# tick-display-mk-5_1.net
KiCad netlist of a schematic drawn in EAGLE
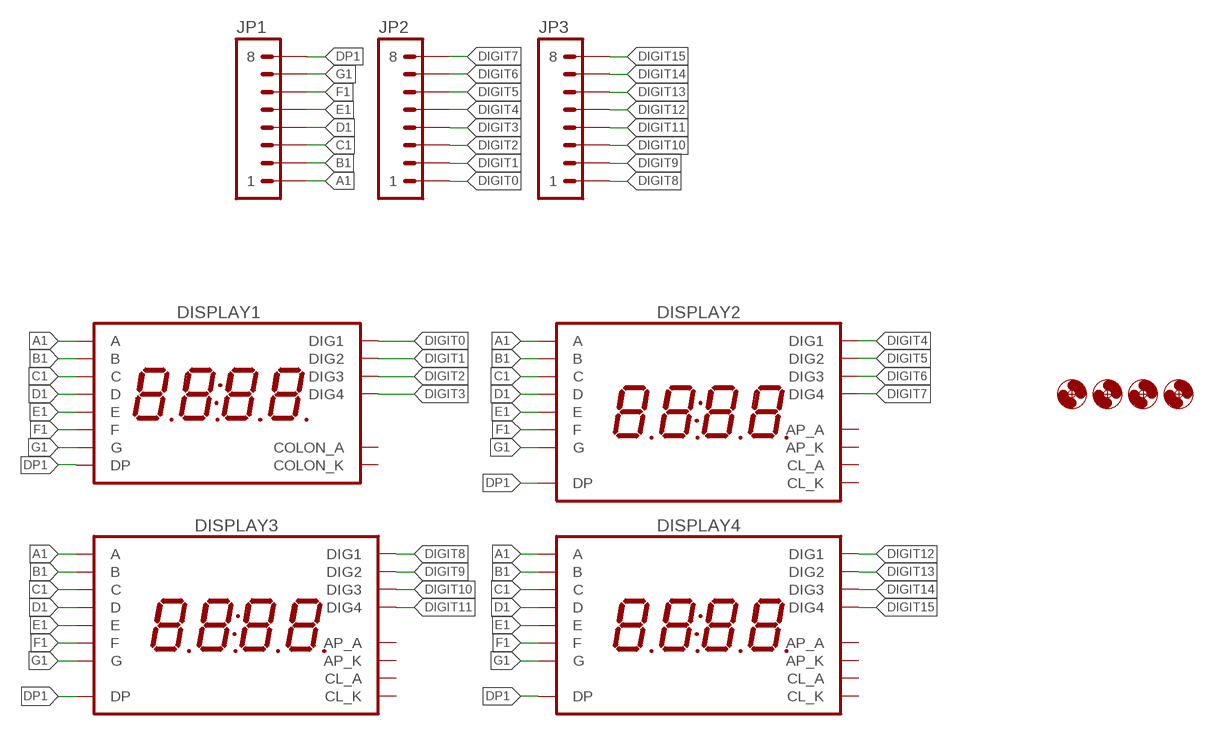
[diagram p0: schematic, sheet 1]

(export (version "E")
  (design (tool "Eeschema 10.0.6"))
  (components
    (comp (ref "DISPLAY1")
      (value "7SEG_4DIGIT_COLON14.2MM-CC")
      (footprint "eagle-import:7SEG_4DIG_0.56IN_14MM_ADAFRUIT")
      (libsource (lib "eagle-import") (part "7SEG_4DIGIT_COLON14.2MM-CC"))
    )
    (comp (ref "DISPLAY2")
      (value "7SEG_4DIGIT_COLON_APOS")
      (footprint "eagle-import:7SEG_4DIG_10MM")
      (libsource (lib "eagle-import") (part "7SEG_4DIGIT_COLON_APOS"))
    )
    (comp (ref "DISPLAY3")
      (value "7SEG_4DIGIT_COLON_APOS")
      (footprint "eagle-import:7SEG_4DIG_10MM")
      (libsource (lib "eagle-import") (part "7SEG_4DIGIT_COLON_APOS"))
    )
    (comp (ref "DISPLAY4")
      (value "7SEG_4DIGIT_COLON_APOS")
      (footprint "eagle-import:7SEG_4DIG_10MM")
      (libsource (lib "eagle-import") (part "7SEG_4DIGIT_COLON_APOS"))
    )
    (comp (ref "H1")
      (value "HOLE#2")
      (footprint "eagle-import:HOLE-#2")
      (libsource (lib "eagle-import") (part "HOLE#2"))
    )
    (comp (ref "H2")
      (value "HOLE#2")
      (footprint "eagle-import:HOLE-#2")
      (libsource (lib "eagle-import") (part "HOLE#2"))
    )
    (comp (ref "H3")
      (value "HOLE#2")
      (footprint "eagle-import:HOLE-#2")
      (libsource (lib "eagle-import") (part "HOLE#2"))
    )
    (comp (ref "H4")
      (value "HOLE#2")
      (footprint "eagle-import:HOLE-#2")
      (libsource (lib "eagle-import") (part "HOLE#2"))
    )
    (comp (ref "JP1")
      (value "M081X08")
      (footprint "eagle-import:1X08")
      (libsource (lib "eagle-import") (part "M081X08"))
    )
    (comp (ref "JP2")
      (value "M081X08")
      (footprint "eagle-import:1X08")
      (libsource (lib "eagle-import") (part "M081X08"))
    )
    (comp (ref "JP3")
      (value "M081X08")
      (footprint "eagle-import:1X08")
      (libsource (lib "eagle-import") (part "M081X08"))
    )
  )
  (nets
    (net (code "1") (name "A1") (class "Default")
      (node (ref "DISPLAY1") (pin "P$13") (pinfunction "A_P$13") (pintype "passive"))
      (node (ref "DISPLAY2") (pin "14") (pinfunction "A_14") (pintype "passive"))
      (node (ref "DISPLAY3") (pin "14") (pinfunction "A_14") (pintype "passive"))
      (node (ref "DISPLAY4") (pin "14") (pinfunction "A_14") (pintype "passive"))
      (node (ref "JP1") (pin "1") (pinfunction "1_1") (pintype "passive"))
    )
    (net (code "2") (name "B1") (class "Default")
      (node (ref "DISPLAY1") (pin "P$9") (pinfunction "B_P$9") (pintype "passive"))
      (node (ref "DISPLAY2") (pin "16") (pinfunction "B_16") (pintype "passive"))
      (node (ref "DISPLAY3") (pin "16") (pinfunction "B_16") (pintype "passive"))
      (node (ref "DISPLAY4") (pin "16") (pinfunction "B_16") (pintype "passive"))
      (node (ref "JP1") (pin "2") (pinfunction "2_2") (pintype "passive"))
    )
    (net (code "3") (name "C1") (class "Default")
      (node (ref "DISPLAY1") (pin "P$4") (pinfunction "C_P$4") (pintype "passive"))
      (node (ref "DISPLAY2") (pin "13") (pinfunction "C_13") (pintype "passive"))
      (node (ref "DISPLAY3") (pin "13") (pinfunction "C_13") (pintype "passive"))
      (node (ref "DISPLAY4") (pin "13") (pinfunction "C_13") (pintype "passive"))
      (node (ref "JP1") (pin "3") (pinfunction "3_3") (pintype "passive"))
    )
    (net (code "4") (name "D1") (class "Default")
      (node (ref "DISPLAY1") (pin "P$2") (pinfunction "D_P$2") (pintype "passive"))
      (node (ref "DISPLAY2") (pin "3") (pinfunction "D_3") (pintype "passive"))
      (node (ref "DISPLAY3") (pin "3") (pinfunction "D_3") (pintype "passive"))
      (node (ref "DISPLAY4") (pin "3") (pinfunction "D_3") (pintype "passive"))
      (node (ref "JP1") (pin "4") (pinfunction "4_4") (pintype "passive"))
    )
    (net (code "5") (name "DIGIT0") (class "Default")
      (node (ref "DISPLAY1") (pin "P$14") (pinfunction "DIG1_P$14") (pintype "passive"))
      (node (ref "JP2") (pin "1") (pinfunction "1_1") (pintype "passive"))
    )
    (net (code "6") (name "DIGIT1") (class "Default")
      (node (ref "DISPLAY1") (pin "P$11") (pinfunction "DIG2_P$11") (pintype "passive"))
      (node (ref "JP2") (pin "2") (pinfunction "2_2") (pintype "passive"))
    )
    (net (code "7") (name "DIGIT2") (class "Default")
      (node (ref "DISPLAY1") (pin "P$10") (pinfunction "DIG3_P$10") (pintype "passive"))
      (node (ref "JP2") (pin "3") (pinfunction "3_3") (pintype "passive"))
    )
    (net (code "8") (name "DIGIT3") (class "Default")
      (node (ref "DISPLAY1") (pin "P$6") (pinfunction "DIG4_P$6") (pintype "passive"))
      (node (ref "JP2") (pin "4") (pinfunction "4_4") (pintype "passive"))
    )
    (net (code "9") (name "DIGIT4") (class "Default")
      (node (ref "DISPLAY2") (pin "1") (pinfunction "DIG1_1") (pintype "passive"))
      (node (ref "JP2") (pin "5") (pinfunction "5_5") (pintype "passive"))
    )
    (net (code "10") (name "DIGIT5") (class "Default")
      (node (ref "DISPLAY2") (pin "2") (pinfunction "DIG2_2") (pintype "passive"))
      (node (ref "JP2") (pin "6") (pinfunction "6_6") (pintype "passive"))
    )
    (net (code "11") (name "DIGIT6") (class "Default")
      (node (ref "DISPLAY2") (pin "6") (pinfunction "DIG3_6") (pintype "passive"))
      (node (ref "JP2") (pin "7") (pinfunction "7_7") (pintype "passive"))
    )
    (net (code "12") (name "DIGIT7") (class "Default")
      (node (ref "DISPLAY2") (pin "8") (pinfunction "DIG4_8") (pintype "passive"))
      (node (ref "JP2") (pin "8") (pinfunction "8_8") (pintype "passive"))
    )
    (net (code "13") (name "DIGIT8") (class "Default")
      (node (ref "DISPLAY3") (pin "1") (pinfunction "DIG1_1") (pintype "passive"))
      (node (ref "JP3") (pin "1") (pinfunction "1_1") (pintype "passive"))
    )
    (net (code "14") (name "DIGIT9") (class "Default")
      (node (ref "DISPLAY3") (pin "2") (pinfunction "DIG2_2") (pintype "passive"))
      (node (ref "JP3") (pin "2") (pinfunction "2_2") (pintype "passive"))
    )
    (net (code "15") (name "DIGIT10") (class "Default")
      (node (ref "DISPLAY3") (pin "6") (pinfunction "DIG3_6") (pintype "passive"))
      (node (ref "JP3") (pin "3") (pinfunction "3_3") (pintype "passive"))
    )
    (net (code "16") (name "DIGIT11") (class "Default")
      (node (ref "DISPLAY3") (pin "8") (pinfunction "DIG4_8") (pintype "passive"))
      (node (ref "JP3") (pin "4") (pinfunction "4_4") (pintype "passive"))
    )
    (net (code "17") (name "DIGIT12") (class "Default")
      (node (ref "DISPLAY4") (pin "1") (pinfunction "DIG1_1") (pintype "passive"))
      (node (ref "JP3") (pin "5") (pinfunction "5_5") (pintype "passive"))
    )
    (net (code "18") (name "DIGIT13") (class "Default")
      (node (ref "DISPLAY4") (pin "2") (pinfunction "DIG2_2") (pintype "passive"))
      (node (ref "JP3") (pin "6") (pinfunction "6_6") (pintype "passive"))
    )
    (net (code "19") (name "DIGIT14") (class "Default")
      (node (ref "DISPLAY4") (pin "6") (pinfunction "DIG3_6") (pintype "passive"))
      (node (ref "JP3") (pin "7") (pinfunction "7_7") (pintype "passive"))
    )
    (net (code "20") (name "DIGIT15") (class "Default")
      (node (ref "DISPLAY4") (pin "8") (pinfunction "DIG4_8") (pintype "passive"))
      (node (ref "JP3") (pin "8") (pinfunction "8_8") (pintype "passive"))
    )
    (net (code "21") (name "DP1") (class "Default")
      (node (ref "DISPLAY1") (pin "P$3") (pinfunction "DP_P$3") (pintype "passive"))
      (node (ref "DISPLAY2") (pin "7") (pinfunction "DP_7") (pintype "passive"))
      (node (ref "DISPLAY3") (pin "7") (pinfunction "DP_7") (pintype "passive"))
      (node (ref "DISPLAY4") (pin "7") (pinfunction "DP_7") (pintype "passive"))
      (node (ref "JP1") (pin "8") (pinfunction "8_8") (pintype "passive"))
    )
    (net (code "22") (name "E1") (class "Default")
      (node (ref "DISPLAY1") (pin "P$1") (pinfunction "E_P$1") (pintype "passive"))
      (node (ref "DISPLAY2") (pin "5") (pinfunction "E_5") (pintype "passive"))
      (node (ref "DISPLAY3") (pin "5") (pinfunction "E_5") (pintype "passive"))
      (node (ref "DISPLAY4") (pin "5") (pinfunction "E_5") (pintype "passive"))
      (node (ref "JP1") (pin "5") (pinfunction "5_5") (pintype "passive"))
    )
    (net (code "23") (name "F1") (class "Default")
      (node (ref "DISPLAY1") (pin "P$12") (pinfunction "F_P$12") (pintype "passive"))
      (node (ref "DISPLAY2") (pin "11") (pinfunction "F_11") (pintype "passive"))
      (node (ref "DISPLAY3") (pin "11") (pinfunction "F_11") (pintype "passive"))
      (node (ref "DISPLAY4") (pin "11") (pinfunction "F_11") (pintype "passive"))
      (node (ref "JP1") (pin "6") (pinfunction "6_6") (pintype "passive"))
    )
    (net (code "24") (name "G1") (class "Default")
      (node (ref "DISPLAY1") (pin "P$5") (pinfunction "G_P$5") (pintype "passive"))
      (node (ref "DISPLAY2") (pin "15") (pinfunction "G_15") (pintype "passive"))
      (node (ref "DISPLAY3") (pin "15") (pinfunction "G_15") (pintype "passive"))
      (node (ref "DISPLAY4") (pin "15") (pinfunction "G_15") (pintype "passive"))
      (node (ref "JP1") (pin "7") (pinfunction "7_7") (pintype "passive"))
    )
    (net (code "25") (name "unconnected-(DISPLAY1-COLON_A-PadP$8)") (class "Default")
      (node (ref "DISPLAY1") (pin "P$8") (pinfunction "COLON_A_P$8") (pintype "passive"))
    )
    (net (code "26") (name "unconnected-(DISPLAY1-COLON_K-PadP$7)") (class "Default")
      (node (ref "DISPLAY1") (pin "P$7") (pinfunction "COLON_K_P$7") (pintype "passive"))
    )
    (net (code "27") (name "unconnected-(DISPLAY2-AP_A-Pad10)") (class "Default")
      (node (ref "DISPLAY2") (pin "10") (pinfunction "AP_A_10") (pintype "bidirectional"))
    )
    (net (code "28") (name "unconnected-(DISPLAY2-AP_K-Pad9)") (class "Default")
      (node (ref "DISPLAY2") (pin "9") (pinfunction "AP_K_9") (pintype "bidirectional"))
    )
    (net (code "29") (name "unconnected-(DISPLAY2-CL_A-Pad4)") (class "Default")
      (node (ref "DISPLAY2") (pin "4") (pinfunction "CL_A_4") (pintype "passive"))
    )
    (net (code "30") (name "unconnected-(DISPLAY2-CL_K-Pad12)") (class "Default")
      (node (ref "DISPLAY2") (pin "12") (pinfunction "CL_K_12") (pintype "passive"))
    )
    (net (code "31") (name "unconnected-(DISPLAY3-AP_A-Pad10)") (class "Default")
      (node (ref "DISPLAY3") (pin "10") (pinfunction "AP_A_10") (pintype "bidirectional"))
    )
    (net (code "32") (name "unconnected-(DISPLAY3-AP_K-Pad9)") (class "Default")
      (node (ref "DISPLAY3") (pin "9") (pinfunction "AP_K_9") (pintype "bidirectional"))
    )
    (net (code "33") (name "unconnected-(DISPLAY3-CL_A-Pad4)") (class "Default")
      (node (ref "DISPLAY3") (pin "4") (pinfunction "CL_A_4") (pintype "passive"))
    )
    (net (code "34") (name "unconnected-(DISPLAY3-CL_K-Pad12)") (class "Default")
      (node (ref "DISPLAY3") (pin "12") (pinfunction "CL_K_12") (pintype "passive"))
    )
    (net (code "35") (name "unconnected-(DISPLAY4-AP_A-Pad10)") (class "Default")
      (node (ref "DISPLAY4") (pin "10") (pinfunction "AP_A_10") (pintype "bidirectional"))
    )
    (net (code "36") (name "unconnected-(DISPLAY4-AP_K-Pad9)") (class "Default")
      (node (ref "DISPLAY4") (pin "9") (pinfunction "AP_K_9") (pintype "bidirectional"))
    )
    (net (code "37") (name "unconnected-(DISPLAY4-CL_A-Pad4)") (class "Default")
      (node (ref "DISPLAY4") (pin "4") (pinfunction "CL_A_4") (pintype "passive"))
    )
    (net (code "38") (name "unconnected-(DISPLAY4-CL_K-Pad12)") (class "Default")
      (node (ref "DISPLAY4") (pin "12") (pinfunction "CL_K_12") (pintype "passive"))
    )
  )
)
